# clock_reset_for_audio_equipment.net
KiCad netlist of a schematic drawn in EAGLE
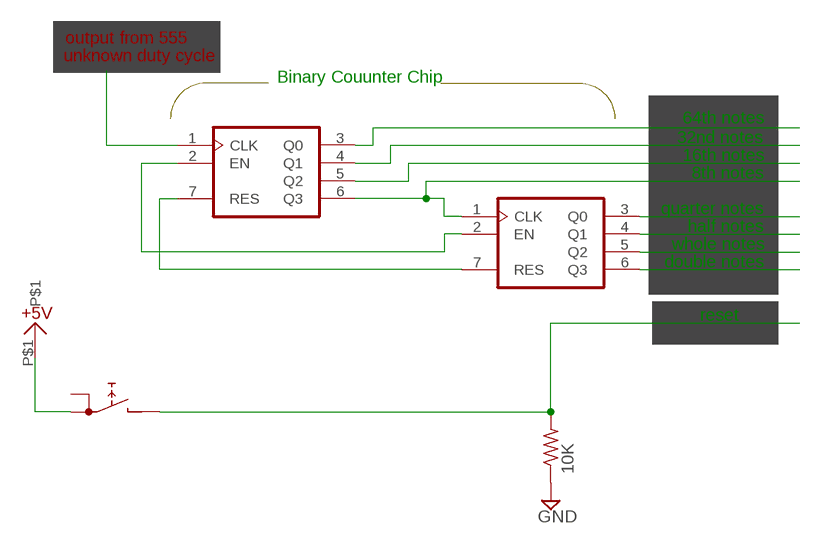
[diagram p0: schematic, sheet 1]

(export (version "E")
  (design (tool "Eeschema 10.0.6"))
  (components
    (comp (ref "IC1")
      (value "4518N")
      (footprint "eagle-import:DIL16")
      (libsource (lib "eagle-import") (part "4518N"))
    )
    (comp (ref "IC2")
      (value "4518N")
      (footprint "eagle-import:DIL16")
      (libsource (lib "eagle-import") (part "4518N"))
    )
    (comp (ref "R1")
      (value "10K")
      (footprint "eagle-import:0204_7")
      (libsource (lib "eagle-import") (part "R-US_0204/7"))
    )
    (comp (ref "S1")
      (value "RDT1034")
      (footprint "eagle-import:RDT1034")
      (libsource (lib "eagle-import") (part "RDT1034"))
    )
    (comp (ref "U$1")
      (value "+5V")
      (footprint "eagle-import:+5V")
      (libsource (lib "eagle-import") (part "+5V"))
    )
  )
  (nets
    (net (code "1") (name "GND") (class "Default")
      (node (ref "R1") (pin "1") (pinfunction "1_1") (pintype "passive"))
    )
    (net (code "2") (name "Net-(IC1A-EN)") (class "Default")
      (node (ref "IC1") (pin "2") (pinfunction "EN_2") (pintype "input"))
      (node (ref "IC2") (pin "2") (pinfunction "EN_2") (pintype "input"))
    )
    (net (code "3") (name "Net-(IC1A-Q3)") (class "Default")
      (node (ref "IC1") (pin "6") (pinfunction "Q3_6") (pintype "output"))
      (node (ref "IC2") (pin "1") (pinfunction "CLK_1") (pintype "input"))
    )
    (net (code "4") (name "Net-(IC1A-RES)") (class "Default")
      (node (ref "IC1") (pin "7") (pinfunction "RES_7") (pintype "input"))
      (node (ref "IC2") (pin "7") (pinfunction "RES_7") (pintype "input"))
    )
    (net (code "5") (name "Net-(R1-Pad2)") (class "Default")
      (node (ref "R1") (pin "2") (pinfunction "2_2") (pintype "passive"))
      (node (ref "S1") (pin "B") (pinfunction "B_B") (pintype "passive"))
    )
    (net (code "6") (name "Net-(S1-PadA1)") (class "Default")
      (node (ref "S1") (pin "A1") (pinfunction "A1_A1") (pintype "passive"))
      (node (ref "U$1") (pin "P$1") (pinfunction "P$1_P$1") (pintype "bidirectional"))
    )
    (net (code "7") (name "unconnected-(IC1A-CLK-Pad1)") (class "Default")
      (node (ref "IC1") (pin "1") (pinfunction "CLK_1") (pintype "input"))
    )
    (net (code "8") (name "unconnected-(IC1A-Q0-Pad3)") (class "Default")
      (node (ref "IC1") (pin "3") (pinfunction "Q0_3") (pintype "output"))
    )
    (net (code "9") (name "unconnected-(IC1A-Q1-Pad4)") (class "Default")
      (node (ref "IC1") (pin "4") (pinfunction "Q1_4") (pintype "output"))
    )
    (net (code "10") (name "unconnected-(IC1A-Q2-Pad5)") (class "Default")
      (node (ref "IC1") (pin "5") (pinfunction "Q2_5") (pintype "output"))
    )
    (net (code "11") (name "unconnected-(IC2A-Q0-Pad3)") (class "Default")
      (node (ref "IC2") (pin "3") (pinfunction "Q0_3") (pintype "output"))
    )
    (net (code "12") (name "unconnected-(IC2A-Q1-Pad4)") (class "Default")
      (node (ref "IC2") (pin "4") (pinfunction "Q1_4") (pintype "output"))
    )
    (net (code "13") (name "unconnected-(IC2A-Q2-Pad5)") (class "Default")
      (node (ref "IC2") (pin "5") (pinfunction "Q2_5") (pintype "output"))
    )
    (net (code "14") (name "unconnected-(IC2A-Q3-Pad6)") (class "Default")
      (node (ref "IC2") (pin "6") (pinfunction "Q3_6") (pintype "output"))
    )
    (net (code "15") (name "unconnected-(S1-PadA)") (class "Default")
      (node (ref "S1") (pin "A") (pinfunction "A_A") (pintype "passive"))
    )
  )
)
